# VSense.net
KiCad netlist of a schematic drawn in Altium Designer
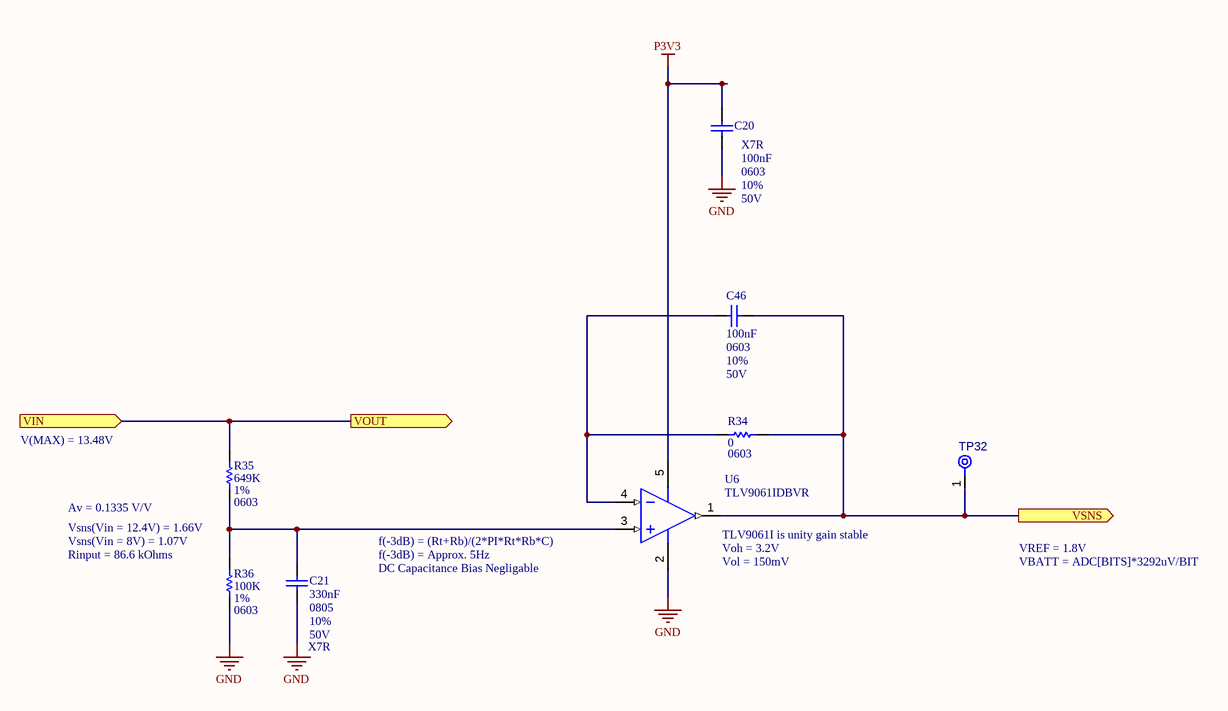
[diagram p0: VSense.SchDoc]

(export (version "E")
  (design (tool "Eeschema 10.0.6"))
  (components
    (comp (ref "C20")
      (value "100nF")
      (footprint "CAPC1608X90X40ML10T20")
      (description "Chip Capacitor, 100nF, +/- 10%, 50 V, X7R 0603 (1608 Metric)")
      (fields
        (field (name "DIELECTRIC") "X7R")
        (field (name "CASE/PACKAGE") "0603")
        (field (name "TOLERANCE") "10%")
        (field (name "VOLTAGE RATING") "50V")
        (field (name "Comment") "Capacitor 100nF +/- 10%, 50V, X7R, 0603")
      )
      (libsource (lib "Applied Physics Lab") (part "CAP-NP-2"))
    )
    (comp (ref "C21")
      (value "330nF")
      (footprint "CAPC2013X95X50ML10T25")
      (description "Chip Capacitor, 330nF, 10%, 50 V, X7R 0805 (2012 Metric)")
      (fields
        (field (name "DIELECTRIC") "X7R")
        (field (name "CASE/PACKAGE") "0805")
        (field (name "TOLERANCE") "10%")
        (field (name "VOLTAGE RATING") "50V")
        (field (name "Comment") "Capacitor 330nF 10%, 50V, X7R, 0805")
      )
      (libsource (lib "Applied Physics Lab") (part "CAP-NP-2"))
    )
    (comp (ref "C46")
      (value "100nF")
      (footprint "CAPC1608X90X40ML10T20")
      (description "Chip Capacitor, 100nF, +/- 10%, 50 V, X7R 0603 (1608 Metric)")
      (fields
        (field (name "CASE/PACKAGE") "0603")
        (field (name "TOLERANCE") "10%")
        (field (name "VOLTAGE RATING") "50V")
        (field (name "Comment") "Capacitor 100nF +/- 10%, 50V, X7R, 0603")
      )
      (libsource (lib "Applied Physics Lab") (part "CAP-NP-2"))
    )
    (comp (ref "R34")
      (value "0")
      (footprint "RESC1608X55X25ML10T15")
      (description "Chip Resistor, 0 Ohm, 0.1 W, -55 to 155 degC, 0603 (1608 Metric)")
      (fields
        (field (name "CASE/PACKAGE") "0603")
        (field (name "TOLERANCE") "5%")
        (field (name "POWER") "100mW")
      )
      (libsource (lib "Applied Physics Lab") (part "RES-2"))
    )
    (comp (ref "R35")
      (value "649K")
      (footprint "RESC1609X50X30ML08T20")
      (description "Chip Resistor, 649k Ohm, +/- 1%, 0.1 W, -55 to 155 degC, 0603 (1608 Metric)")
      (fields
        (field (name "TOLERANCE") "1%")
        (field (name "POWER") "100mW")
        (field (name "CASE/PACKAGE") "0603")
        (field (name "Comment") "Resistor 649K +/-1% 0603 100 mW")
      )
      (libsource (lib "Applied Physics Lab") (part "RES-2"))
    )
    (comp (ref "R36")
      (value "100K")
      (footprint "RESC1609X50X30ML08T20")
      (description "Chip Resistor, 100k Ohm, +/- 1%, 0.1 W, -55 to 155 degC, 0603 (1608 Metric)")
      (fields
        (field (name "CASE/PACKAGE") "0603")
        (field (name "TOLERANCE") "1%")
        (field (name "POWER") "100mW")
        (field (name "Comment") "Resistor 100K +/-1% 0603 100 mW")
      )
      (libsource (lib "Applied Physics Lab") (part "RES-2"))
    )
    (comp (ref "TP32")
      (value "TPAD6R-CIRCLED")
      (footprint "TP06R - Circled")
      (description "0.6mm round with a silkscreen circle.")
      (libsource (lib "Applied Physics Lab") (part "CMP-001-0001-4"))
    )
    (comp (ref "U6")
      (value "TLV9061IDBVR")
      (footprint "DBV0005A_L")
      (fields (field (name "MANUFACTURER") "Texas Instruments"))
      (libsource (lib "Applied Physics Lab") (part "TI-TLV2XX1DBV5"))
    )
  )
  (nets
    (net (code "1") (name "/VIN") (class "Default")
      (node (ref "R35") (pin "1") (pinfunction "1_1") (pintype "passive"))
    )
    (net (code "2") (name "/VSNS") (class "Default")
      (node (ref "C46") (pin "1") (pinfunction "1_1") (pintype "passive"))
      (node (ref "R34") (pin "2") (pinfunction "2_2") (pintype "passive"))
      (node (ref "TP32") (pin "1") (pinfunction "TP_1") (pintype "passive"))
      (node (ref "U6") (pin "1") (pinfunction "OUT_1") (pintype "output"))
    )
    (net (code "3") (name "GND") (class "Default")
      (node (ref "C20") (pin "1") (pinfunction "1_1") (pintype "passive"))
      (node (ref "C21") (pin "1") (pinfunction "1_1") (pintype "passive"))
      (node (ref "R36") (pin "2") (pinfunction "2_2") (pintype "passive"))
      (node (ref "U6") (pin "2") (pinfunction "GND_2") (pintype "power_in"))
    )
    (net (code "4") (name "Net-(U6-IN+)") (class "Default")
      (node (ref "C21") (pin "2") (pinfunction "2_2") (pintype "passive"))
      (node (ref "R35") (pin "2") (pinfunction "2_2") (pintype "passive"))
      (node (ref "R36") (pin "1") (pinfunction "1_1") (pintype "passive"))
      (node (ref "U6") (pin "3") (pinfunction "IN+_3") (pintype "input"))
    )
    (net (code "5") (name "Net-(U6-IN-)") (class "Default")
      (node (ref "C46") (pin "2") (pinfunction "2_2") (pintype "passive"))
      (node (ref "R34") (pin "1") (pinfunction "1_1") (pintype "passive"))
      (node (ref "U6") (pin "4") (pinfunction "IN-_4") (pintype "input"))
    )
    (net (code "6") (name "P3V3") (class "Default")
      (node (ref "C20") (pin "2") (pinfunction "2_2") (pintype "passive"))
      (node (ref "U6") (pin "5") (pinfunction "VDD_5") (pintype "power_in"))
    )
  )
)
